# MCU.net
KiCad netlist of a schematic drawn in Altium Designer
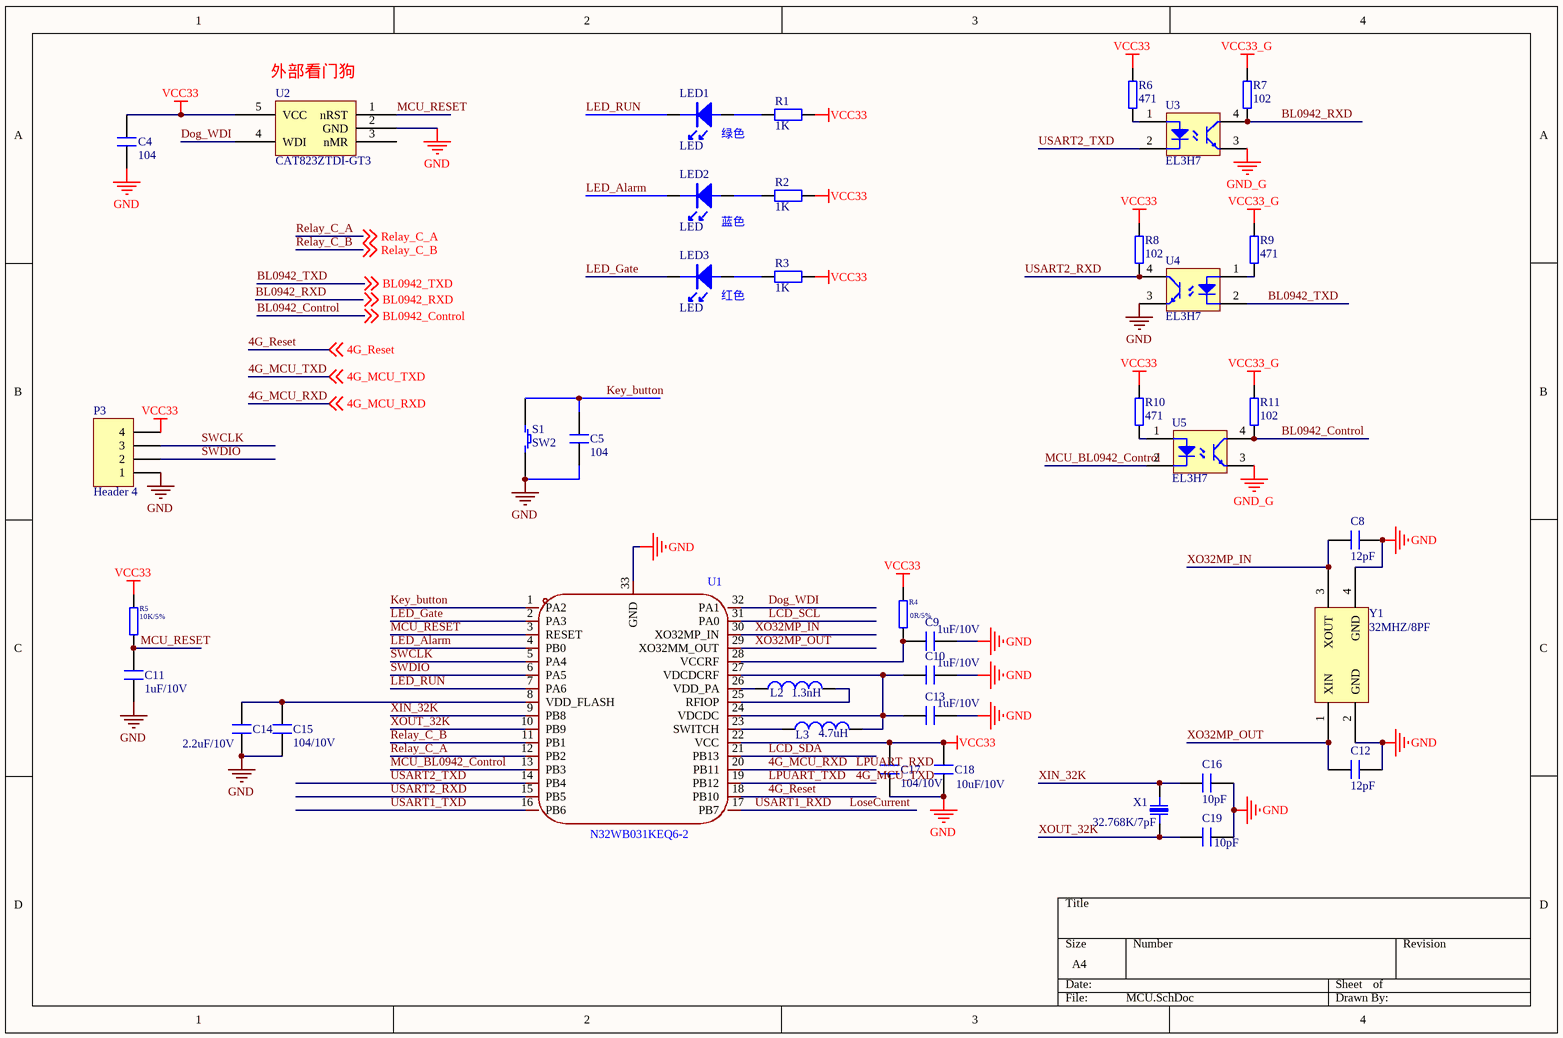
[diagram p0: MCU.SchDoc]

(export (version "E")
  (design (tool "Eeschema 10.0.6"))
  (components
    (comp (ref "C4") (value "104") (footprint "0603R") (libsource (lib "ES_Schematic") (part "CAP")))
    (comp (ref "C5") (value "104") (footprint "0603R") (libsource (lib "ES_Schematic") (part "CAP")))
    (comp (ref "C8") (value "12pF") (footprint "0603r") (libsource (lib "ES_Schematic") (part "CAP")))
    (comp (ref "C9") (value "1uF/10V") (footprint "0603R") (libsource (lib "ES_Schematic") (part "CAP_1")))
    (comp (ref "C10") (value "1uF/10V") (footprint "0603R") (libsource (lib "ES_Schematic") (part "CAP_1")))
    (comp (ref "C11") (value "1uF/10V") (footprint "0603R") (libsource (lib "ES_Schematic") (part "CAP_1")))
    (comp (ref "C12") (value "12pF") (footprint "0603r") (libsource (lib "ES_Schematic") (part "CAP")))
    (comp (ref "C13") (value "1uF/10V") (footprint "0603R") (libsource (lib "ES_Schematic") (part "CAP_1")))
    (comp (ref "C14") (value "2.2uF/10V") (footprint "0603R") (libsource (lib "ES_Schematic") (part "CAP_1")))
    (comp (ref "C15") (value "104/10V") (footprint "0603R") (libsource (lib "ES_Schematic") (part "CAP_1")))
    (comp (ref "C16") (value "10pF") (footprint "0603r") (libsource (lib "ES_Schematic") (part "CAP")))
    (comp (ref "C17") (value "104/10V") (footprint "0603R") (libsource (lib "ES_Schematic") (part "CAP_1")))
    (comp (ref "C18") (value "10uF/10V") (footprint "0603R") (libsource (lib "ES_Schematic") (part "CAP_1")))
    (comp (ref "C19") (value "10pF") (footprint "0603r") (libsource (lib "ES_Schematic") (part "CAP")))
    (comp (ref "L2")
      (value "1.3nH")
      (footprint "0603R")
      (description "Inductor")
      (fields (field (name "PUBLISHER") "Altium Limited"))
      (libsource (lib "Miscellaneous Devices") (part "Inductor"))
    )
    (comp (ref "L3")
      (value "4.7uH")
      (footprint "0603R")
      (description "Inductor")
      (fields (field (name "PUBLISHER") "Altium Limited"))
      (libsource (lib "Miscellaneous Devices") (part "Inductor"))
    )
    (comp (ref "LED1") (value "LED") (footprint "LED0805") (libsource (lib "ES_Schematic") (part "LED")))
    (comp (ref "LED2") (value "LED") (footprint "LED0805") (libsource (lib "ES_Schematic") (part "LED")))
    (comp (ref "LED3") (value "LED") (footprint "LED0805") (libsource (lib "ES_Schematic") (part "LED")))
    (comp (ref "P3")
      (value "Header 4")
      (footprint "HDR1X4")
      (description "Header, 4-Pin")
      (fields (field (name "PUBLISHER") "Altium Limited"))
      (libsource (lib "Miscellaneous Connectors") (part "Header 4"))
    )
    (comp (ref "R1")
      (value "1K")
      (footprint "0603R")
      (fields (field (name "Comment") "Res2") (field (name "PUBLISHER") "Altium Limited"))
      (libsource (lib "Miscellaneous Devices") (part "Res2"))
    )
    (comp (ref "R2")
      (value "1K")
      (footprint "0603R")
      (fields (field (name "Comment") "Res2") (field (name "PUBLISHER") "Altium Limited"))
      (libsource (lib "Miscellaneous Devices") (part "Res2"))
    )
    (comp (ref "R3")
      (value "1K")
      (footprint "0603R")
      (fields (field (name "Comment") "Res2") (field (name "PUBLISHER") "Altium Limited"))
      (libsource (lib "Miscellaneous Devices") (part "Res2"))
    )
    (comp (ref "R4") (value "0R/5%") (footprint "0603R") (libsource (lib "ES_Schematic") (part "RES")))
    (comp (ref "R5") (value "10K/5%") (footprint "0603R") (libsource (lib "ES_Schematic") (part "RES")))
    (comp (ref "R6") (value "471") (footprint "0603R") (libsource (lib "ES_Schematic") (part "RES")))
    (comp (ref "R7") (value "102") (footprint "0603R") (libsource (lib "ES_Schematic") (part "RES")))
    (comp (ref "R8") (value "102") (footprint "0603R") (libsource (lib "ES_Schematic") (part "RES")))
    (comp (ref "R9") (value "471") (footprint "0603R") (libsource (lib "ES_Schematic") (part "RES")))
    (comp (ref "R10") (value "471") (footprint "0603R") (libsource (lib "ES_Schematic") (part "RES")))
    (comp (ref "R11") (value "102") (footprint "0603R") (libsource (lib "ES_Schematic") (part "RES")))
    (comp (ref "S1")
      (value "SW2")
      (footprint "4.5*4.5贴片4脚独立按键")
      (libsource (lib "ES_Schematic") (part "SW2"))
    )
    (comp (ref "U1")
      (value "N32WB031KEQ6-2")
      (footprint "QFN-32_L4.0-W4.0-P0.40-TL-EP2.8")
      (fields (field (name "MANUFACTURER") "Nations(国民技术)"))
      (libsource (lib "altium-import") (part "root_0_N32WB031KEQ6-2_"))
    )
    (comp (ref "U2")
      (value "CAT823ZTDI-GT3")
      (footprint "SOT-23-5")
      (libsource (lib "ES_Schematic") (part "CAT823"))
    )
    (comp (ref "U3")
      (value "EL3H7")
      (footprint "EL3H7")
      (libsource (lib "ES_Schematic") (part "Optical_Coupler_1"))
    )
    (comp (ref "U4") (value "EL3H7") (footprint "EL3H7") (libsource (lib "") (part "Optical_Coupler_1_1")))
    (comp (ref "U5")
      (value "EL3H7")
      (footprint "EL3H7")
      (libsource (lib "ES_Schematic") (part "Optical_Coupler_1"))
    )
    (comp (ref "X1") (value "32.768K/7pF") (footprint "Y3215") (libsource (lib "ES_Schematic") (part "XTAL")))
    (comp (ref "Y1") (value "32MHZ/8PF") (footprint "3225") (libsource (lib "others") (part "12MHz无源")))
  )
  (nets
    (net (code "1") (name "/Dog_WDI") (class "Default")
      (node (ref "U1") (pin "32") (pinfunction "PA1_32") (pintype "passive"))
      (node (ref "U2") (pin "4") (pinfunction "WDI_4") (pintype "passive"))
    )
    (net (code "2") (name "/Key_button") (class "Default")
      (node (ref "C5") (pin "1") (pinfunction "1_1") (pintype "passive"))
      (node (ref "S1") (pin "1") (pinfunction "1_1") (pintype "passive"))
      (node (ref "U1") (pin "1") (pinfunction "PA2_1") (pintype "passive"))
    )
    (net (code "3") (name "/LCD_SCL") (class "Default")
      (node (ref "U1") (pin "31") (pinfunction "PA0_31") (pintype "passive"))
    )
    (net (code "4") (name "/LCD_SDA") (class "Default")
      (node (ref "U1") (pin "21") (pinfunction "PB13_21") (pintype "passive"))
    )
    (net (code "5") (name "/LED_Alarm") (class "Default")
      (node (ref "LED2") (pin "2") (pinfunction "2_2") (pintype "passive"))
      (node (ref "U1") (pin "4") (pinfunction "PB0_4") (pintype "passive"))
    )
    (net (code "6") (name "/LED_Gate") (class "Default")
      (node (ref "LED3") (pin "2") (pinfunction "2_2") (pintype "passive"))
      (node (ref "U1") (pin "2") (pinfunction "PA3_2") (pintype "passive"))
    )
    (net (code "7") (name "/LED_RUN") (class "Default")
      (node (ref "LED1") (pin "2") (pinfunction "2_2") (pintype "passive"))
      (node (ref "U1") (pin "7") (pinfunction "PA6_7") (pintype "passive"))
    )
    (net (code "8") (name "/LoseCurrent") (class "Default")
      (node (ref "U1") (pin "17") (pinfunction "PB7_17") (pintype "passive"))
    )
    (net (code "9") (name "/MCU_BL0942_Control") (class "Default")
      (node (ref "U1") (pin "13") (pinfunction "PB3_13") (pintype "passive"))
      (node (ref "U5") (pin "2") (pinfunction "K_2") (pintype "passive"))
    )
    (net (code "10") (name "/MCU_RESET") (class "Default")
      (node (ref "C11") (pin "2") (pinfunction "2_2") (pintype "passive"))
      (node (ref "R5") (pin "2") (pinfunction "2_2") (pintype "passive"))
      (node (ref "U1") (pin "3") (pinfunction "RESET_3") (pintype "passive"))
      (node (ref "U2") (pin "1") (pinfunction "nRST_1") (pintype "passive"))
    )
    (net (code "11") (name "/SWCLK") (class "Default")
      (node (ref "P3") (pin "3") (pinfunction "3_3") (pintype "passive"))
      (node (ref "U1") (pin "5") (pinfunction "PA4_5") (pintype "passive"))
    )
    (net (code "12") (name "/SWDIO") (class "Default")
      (node (ref "P3") (pin "2") (pinfunction "2_2") (pintype "passive"))
      (node (ref "U1") (pin "6") (pinfunction "PA5_6") (pintype "passive"))
    )
    (net (code "13") (name "/USART1_TXD") (class "Default")
      (node (ref "U1") (pin "16") (pinfunction "PB6_16") (pintype "passive"))
    )
    (net (code "14") (name "/USART2_RXD") (class "Default")
      (node (ref "R8") (pin "1") (pinfunction "1_1") (pintype "passive"))
      (node (ref "U1") (pin "15") (pinfunction "PB5_15") (pintype "passive"))
      (node (ref "U4") (pin "4") (pinfunction "C_4") (pintype "passive"))
    )
    (net (code "15") (name "/USART2_TXD") (class "Default")
      (node (ref "U1") (pin "14") (pinfunction "PB4_14") (pintype "passive"))
      (node (ref "U3") (pin "2") (pinfunction "K_2") (pintype "passive"))
    )
    (net (code "16") (name "/XIN_32K") (class "Default")
      (node (ref "C16") (pin "1") (pinfunction "1_1") (pintype "passive"))
      (node (ref "U1") (pin "9") (pinfunction "PB8_9") (pintype "passive"))
      (node (ref "X1") (pin "2") (pinfunction "2_2") (pintype "passive"))
    )
    (net (code "17") (name "/XO32MP_IN") (class "Default")
      (node (ref "C8") (pin "2") (pinfunction "2_2") (pintype "passive"))
      (node (ref "U1") (pin "30") (pinfunction "XO32MP_IN_30") (pintype "passive"))
      (node (ref "Y1") (pin "3") (pinfunction "XOUT_3") (pintype "passive"))
    )
    (net (code "18") (name "/XO32MP_OUT") (class "Default")
      (node (ref "C12") (pin "2") (pinfunction "2_2") (pintype "passive"))
      (node (ref "U1") (pin "29") (pinfunction "XO32MM_OUT_29") (pintype "passive"))
      (node (ref "Y1") (pin "1") (pinfunction "XIN_1") (pintype "passive"))
    )
    (net (code "19") (name "/XOUT_32K") (class "Default")
      (node (ref "C19") (pin "2") (pinfunction "2_2") (pintype "passive"))
      (node (ref "U1") (pin "10") (pinfunction "PB9_10") (pintype "passive"))
      (node (ref "X1") (pin "1") (pinfunction "1_1") (pintype "passive"))
    )
    (net (code "20") (name "4G_MCU_RXD") (class "Default")
      (node (ref "U1") (pin "20") (pinfunction "PB11_20") (pintype "passive"))
    )
    (net (code "21") (name "4G_MCU_TXD") (class "Default")
      (node (ref "U1") (pin "19") (pinfunction "PB12_19") (pintype "passive"))
    )
    (net (code "22") (name "4G_Reset") (class "Default")
      (node (ref "U1") (pin "18") (pinfunction "PB10_18") (pintype "passive"))
    )
    (net (code "23") (name "BL0942_Control") (class "Default")
      (node (ref "R11") (pin "1") (pinfunction "1_1") (pintype "passive"))
      (node (ref "U5") (pin "4") (pinfunction "C_4") (pintype "passive"))
    )
    (net (code "24") (name "BL0942_RXD") (class "Default")
      (node (ref "R7") (pin "1") (pinfunction "1_1") (pintype "passive"))
      (node (ref "U3") (pin "4") (pinfunction "C_4") (pintype "passive"))
    )
    (net (code "25") (name "BL0942_TXD") (class "Default")
      (node (ref "U4") (pin "2") (pinfunction "K_2") (pintype "passive"))
    )
    (net (code "26") (name "GND") (class "Default")
      (node (ref "C10") (pin "1") (pinfunction "1_1") (pintype "passive"))
      (node (ref "C11") (pin "1") (pinfunction "1_1") (pintype "passive"))
      (node (ref "C12") (pin "1") (pinfunction "1_1") (pintype "passive"))
      (node (ref "C13") (pin "1") (pinfunction "1_1") (pintype "passive"))
      (node (ref "C14") (pin "1") (pinfunction "1_1") (pintype "passive"))
      (node (ref "C15") (pin "1") (pinfunction "1_1") (pintype "passive"))
      (node (ref "C16") (pin "2") (pinfunction "2_2") (pintype "passive"))
      (node (ref "C17") (pin "1") (pinfunction "1_1") (pintype "passive"))
      (node (ref "C18") (pin "1") (pinfunction "1_1") (pintype "passive"))
      (node (ref "C19") (pin "1") (pinfunction "1_1") (pintype "passive"))
      (node (ref "C4") (pin "1") (pinfunction "1_1") (pintype "passive"))
      (node (ref "C5") (pin "2") (pinfunction "2_2") (pintype "passive"))
      (node (ref "C8") (pin "1") (pinfunction "1_1") (pintype "passive"))
      (node (ref "C9") (pin "1") (pinfunction "1_1") (pintype "passive"))
      (node (ref "P3") (pin "1") (pinfunction "1_1") (pintype "passive"))
      (node (ref "S1") (pin "2") (pinfunction "2_2") (pintype "passive"))
      (node (ref "U1") (pin "33") (pinfunction "GND_33") (pintype "passive"))
      (node (ref "U2") (pin "2") (pinfunction "GND_2") (pintype "passive"))
      (node (ref "U4") (pin "3") (pinfunction "E_3") (pintype "passive"))
      (node (ref "Y1") (pin "2") (pinfunction "GND_2") (pintype "passive"))
      (node (ref "Y1") (pin "4") (pinfunction "GND_4") (pintype "passive"))
    )
    (net (code "27") (name "GND_G") (class "Default")
      (node (ref "U3") (pin "3") (pinfunction "E_3") (pintype "passive"))
      (node (ref "U5") (pin "3") (pinfunction "E_3") (pintype "passive"))
    )
    (net (code "28") (name "Net-(LED1-Pad1)") (class "Default")
      (node (ref "LED1") (pin "1") (pinfunction "1_1") (pintype "passive"))
      (node (ref "R1") (pin "2") (pinfunction "2_2") (pintype "passive"))
    )
    (net (code "29") (name "Net-(LED2-Pad1)") (class "Default")
      (node (ref "LED2") (pin "1") (pinfunction "1_1") (pintype "passive"))
      (node (ref "R2") (pin "2") (pinfunction "2_2") (pintype "passive"))
    )
    (net (code "30") (name "Net-(LED3-Pad1)") (class "Default")
      (node (ref "LED3") (pin "1") (pinfunction "1_1") (pintype "passive"))
      (node (ref "R3") (pin "2") (pinfunction "2_2") (pintype "passive"))
    )
    (net (code "31") (name "Net-(U1-RFIOP)") (class "Default")
      (node (ref "L2") (pin "2") (pinfunction "2_2") (pintype "passive"))
      (node (ref "U1") (pin "25") (pinfunction "RFIOP_25") (pintype "passive"))
    )
    (net (code "32") (name "Net-(U1-SWITCH)") (class "Default")
      (node (ref "L3") (pin "1") (pinfunction "1_1") (pintype "passive"))
      (node (ref "U1") (pin "23") (pinfunction "SWITCH_23") (pintype "passive"))
    )
    (net (code "33") (name "Net-(U1-VCCRF)") (class "Default")
      (node (ref "C9") (pin "2") (pinfunction "2_2") (pintype "passive"))
      (node (ref "R4") (pin "2") (pinfunction "2_2") (pintype "passive"))
      (node (ref "U1") (pin "28") (pinfunction "VCCRF_28") (pintype "passive"))
    )
    (net (code "34") (name "Net-(U1-VDCDC)") (class "Default")
      (node (ref "C10") (pin "2") (pinfunction "2_2") (pintype "passive"))
      (node (ref "C13") (pin "2") (pinfunction "2_2") (pintype "passive"))
      (node (ref "L3") (pin "2") (pinfunction "2_2") (pintype "passive"))
      (node (ref "U1") (pin "24") (pinfunction "VDCDC_24") (pintype "passive"))
      (node (ref "U1") (pin "27") (pinfunction "VDCDCRF_27") (pintype "passive"))
    )
    (net (code "35") (name "Net-(U1-VDD_FLASH)") (class "Default")
      (node (ref "C14") (pin "2") (pinfunction "2_2") (pintype "passive"))
      (node (ref "C15") (pin "2") (pinfunction "2_2") (pintype "passive"))
      (node (ref "U1") (pin "8") (pinfunction "VDD_FLASH_8") (pintype "passive"))
    )
    (net (code "36") (name "Net-(U1-VDD_PA)") (class "Default")
      (node (ref "L2") (pin "1") (pinfunction "1_1") (pintype "passive"))
      (node (ref "U1") (pin "26") (pinfunction "VDD_PA_26") (pintype "passive"))
    )
    (net (code "37") (name "Net-(U3-A)") (class "Default")
      (node (ref "R6") (pin "2") (pinfunction "2_2") (pintype "passive"))
      (node (ref "U3") (pin "1") (pinfunction "A_1") (pintype "passive"))
    )
    (net (code "38") (name "Net-(U4-A)") (class "Default")
      (node (ref "R9") (pin "2") (pinfunction "2_2") (pintype "passive"))
      (node (ref "U4") (pin "1") (pinfunction "A_1") (pintype "passive"))
    )
    (net (code "39") (name "Net-(U5-A)") (class "Default")
      (node (ref "R10") (pin "2") (pinfunction "2_2") (pintype "passive"))
      (node (ref "U5") (pin "1") (pinfunction "A_1") (pintype "passive"))
    )
    (net (code "40") (name "Relay_C_A") (class "Default")
      (node (ref "U1") (pin "12") (pinfunction "PB2_12") (pintype "passive"))
    )
    (net (code "41") (name "Relay_C_B") (class "Default")
      (node (ref "U1") (pin "11") (pinfunction "PB1_11") (pintype "passive"))
    )
    (net (code "42") (name "VCC33") (class "Default")
      (node (ref "C17") (pin "2") (pinfunction "2_2") (pintype "passive"))
      (node (ref "C18") (pin "2") (pinfunction "2_2") (pintype "passive"))
      (node (ref "C4") (pin "2") (pinfunction "2_2") (pintype "passive"))
      (node (ref "P3") (pin "4") (pinfunction "4_4") (pintype "passive"))
      (node (ref "R1") (pin "1") (pinfunction "1_1") (pintype "passive"))
      (node (ref "R10") (pin "1") (pinfunction "1_1") (pintype "passive"))
      (node (ref "R2") (pin "1") (pinfunction "1_1") (pintype "passive"))
      (node (ref "R3") (pin "1") (pinfunction "1_1") (pintype "passive"))
      (node (ref "R4") (pin "1") (pinfunction "1_1") (pintype "passive"))
      (node (ref "R5") (pin "1") (pinfunction "1_1") (pintype "passive"))
      (node (ref "R6") (pin "1") (pinfunction "1_1") (pintype "passive"))
      (node (ref "R8") (pin "2") (pinfunction "2_2") (pintype "passive"))
      (node (ref "U1") (pin "22") (pinfunction "VCC_22") (pintype "passive"))
      (node (ref "U2") (pin "5") (pinfunction "VCC_5") (pintype "passive"))
    )
    (net (code "43") (name "VCC33_G") (class "Default")
      (node (ref "R11") (pin "2") (pinfunction "2_2") (pintype "passive"))
      (node (ref "R7") (pin "2") (pinfunction "2_2") (pintype "passive"))
      (node (ref "R9") (pin "1") (pinfunction "1_1") (pintype "passive"))
    )
    (net (code "44") (name "unconnected-(U2-nMR-Pad3)") (class "Default")
      (node (ref "U2") (pin "3") (pinfunction "nMR_3") (pintype "passive"))
    )
  )
)
